# Discharge_Board.net
KiCad netlist of a schematic drawn in EAGLE
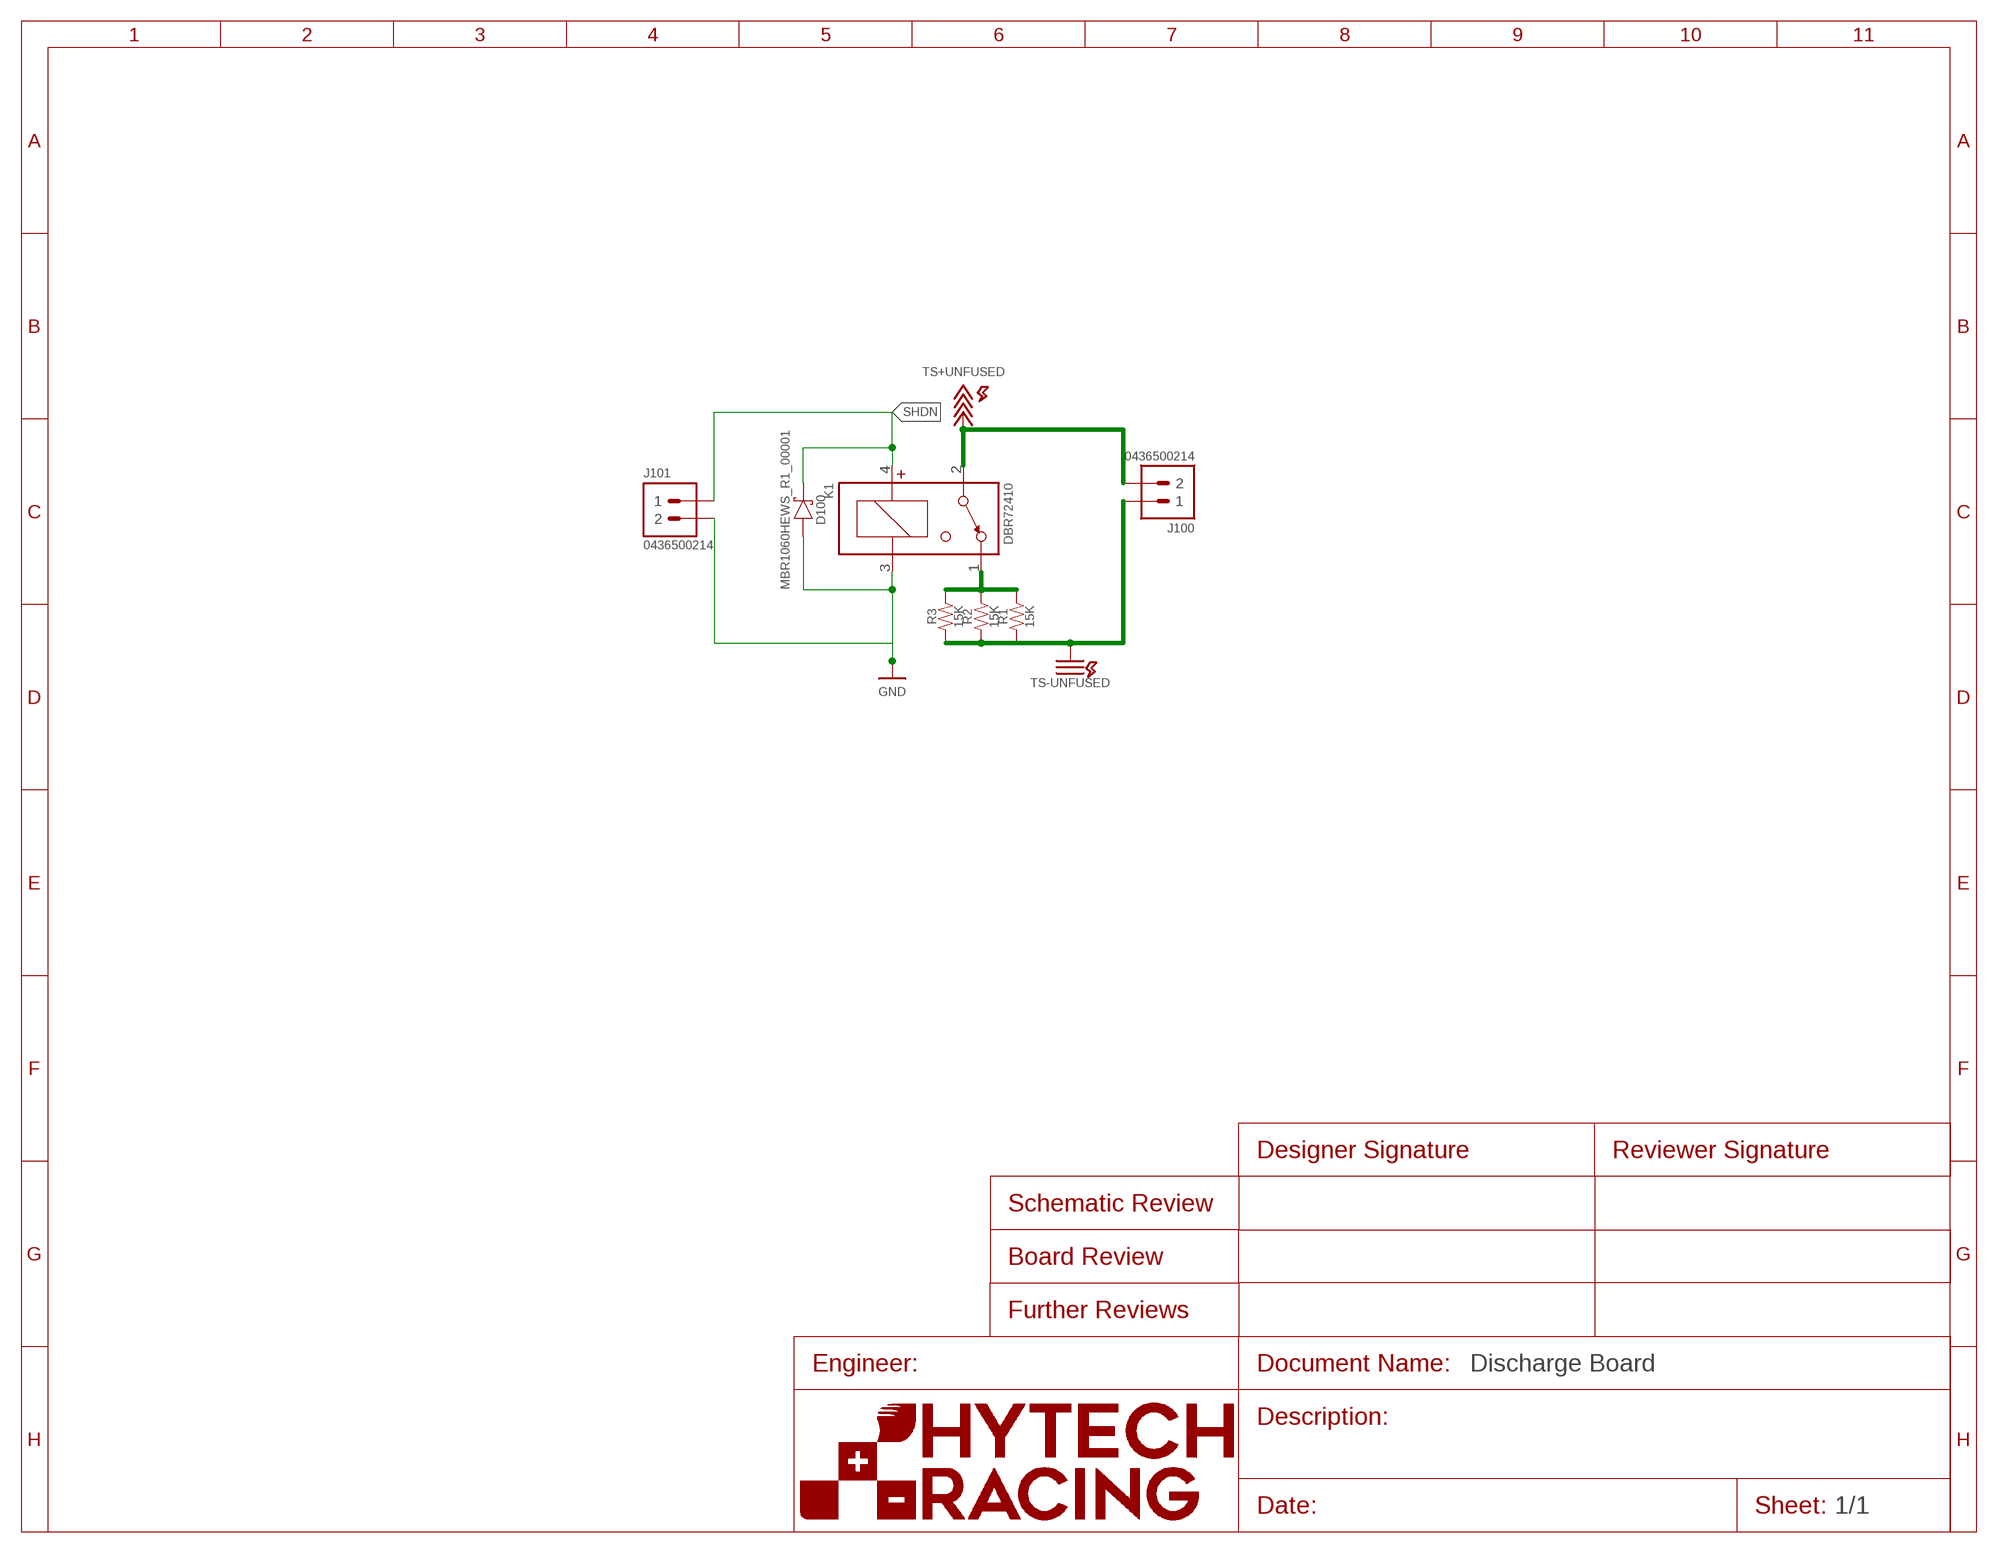
[diagram p0: schematic, sheet 1]

(export (version "E")
  (design (tool "Eeschema 10.0.6"))
  (components
    (comp (ref "D100")
      (value "SCHOTTKY_SOD323_60V")
      (footprint "eagle-import:SOD-323")
      (fields
        (field (name "MANUFACTURER") "Panjit International Inc.")
        (field (name "MPN") "MBR1060HEWS_R1_00001")
        (field (name "VOLTAGE") "60V")
      )
      (libsource (lib "eagle-import") (part "SCHOTTKY_?_SOD32360V"))
    )
    (comp (ref "J100")
      (value "CONNECTOR-2_MICROFIT_SMD_RIGHTANGLE_02_SINGLE_BLACK")
      (footprint "eagle-import:MOLEX_MICROFIT_SMD_RIGHTANGLE_02_SINGLE")
      (fields (field (name "MANUFACTURER") "Molex") (field (name "MPN") "0436500214"))
      (libsource (lib "eagle-import") (part "CONNECTOR-2_?_MICROFIT_SMD_RIGHTANGLE_02_SINGLEBLACK"))
    )
    (comp (ref "J101")
      (value "CONNECTOR-2_MICROFIT_SMD_RIGHTANGLE_02_SINGLE_BLACK")
      (footprint "eagle-import:MOLEX_MICROFIT_SMD_RIGHTANGLE_02_SINGLE")
      (fields (field (name "MANUFACTURER") "Molex") (field (name "MPN") "0436500214"))
      (libsource (lib "eagle-import") (part "CONNECTOR-2_?_MICROFIT_SMD_RIGHTANGLE_02_SINGLEBLACK"))
    )
    (comp (ref "K1")
      (value "RELAY_SPST_NC_POLARIZED_D_24")
      (footprint "eagle-import:D")
      (fields (field (name "MANUFACTURER") "Sensata-Cynergy3") (field (name "MPN") "DBR72410"))
      (libsource (lib "eagle-import") (part "RELAY_SPST_NC_POLARIZED_?D_24"))
    )
    (comp (ref "R1")
      (value "RESISTOR_B20-SHORTENED_15K")
      (footprint "eagle-import:B20-SHORTENED")
      (fields
        (field (name "MANUFACTURER") "Ohmite")
        (field (name "MPN") "B20J15KE")
        (field (name "POWER") "20W")
        (field (name "RESISTANCE") "15K")
      )
      (libsource (lib "eagle-import") (part "RESISTOR_?_B20-SHORTENED15K"))
    )
    (comp (ref "R2")
      (value "RESISTOR_B20-SHORTENED_15K")
      (footprint "eagle-import:B20-SHORTENED")
      (fields
        (field (name "MANUFACTURER") "Ohmite")
        (field (name "MPN") "B20J15KE")
        (field (name "POWER") "20W")
        (field (name "RESISTANCE") "15K")
      )
      (libsource (lib "eagle-import") (part "RESISTOR_?_B20-SHORTENED15K"))
    )
    (comp (ref "R3")
      (value "RESISTOR_B20-SHORTENED_15K")
      (footprint "eagle-import:B20-SHORTENED")
      (fields
        (field (name "MANUFACTURER") "Ohmite")
        (field (name "MPN") "B20J15KE")
        (field (name "POWER") "20W")
        (field (name "RESISTANCE") "15K")
      )
      (libsource (lib "eagle-import") (part "RESISTOR_?_B20-SHORTENED15K"))
    )
  )
  (nets
    (net (code "1") (name "GND") (class "Default")
      (node (ref "D100") (pin "A") (pinfunction "A_A") (pintype "passive"))
      (node (ref "J101") (pin "2") (pinfunction "2_2") (pintype "passive"))
      (node (ref "K1") (pin "3") (pinfunction "COIL-_3") (pintype "bidirectional"))
    )
    (net (code "2") (name "Net-(K1-CONTACT2)") (class "Default")
      (node (ref "K1") (pin "1") (pinfunction "CONTACT2_1") (pintype "bidirectional"))
      (node (ref "R1") (pin "2") (pinfunction "2_2") (pintype "passive"))
      (node (ref "R2") (pin "2") (pinfunction "2_2") (pintype "passive"))
      (node (ref "R3") (pin "2") (pinfunction "2_2") (pintype "passive"))
    )
    (net (code "3") (name "SHDN") (class "Default")
      (node (ref "D100") (pin "C") (pinfunction "C_C") (pintype "passive"))
      (node (ref "J101") (pin "1") (pinfunction "1_1") (pintype "passive"))
      (node (ref "K1") (pin "4") (pinfunction "COIL+_4") (pintype "bidirectional"))
    )
    (net (code "4") (name "TS+UNFUSED") (class "Default")
      (node (ref "J100") (pin "2") (pinfunction "2_2") (pintype "passive"))
      (node (ref "K1") (pin "2") (pinfunction "CONTACT1_2") (pintype "bidirectional"))
    )
    (net (code "5") (name "TS-UNFUSED") (class "Default")
      (node (ref "J100") (pin "1") (pinfunction "1_1") (pintype "passive"))
      (node (ref "R1") (pin "1") (pinfunction "1_1") (pintype "passive"))
      (node (ref "R2") (pin "1") (pinfunction "1_1") (pintype "passive"))
      (node (ref "R3") (pin "1") (pinfunction "1_1") (pintype "passive"))
    )
  )
)
